# Fan_Module.net
KiCad netlist of a schematic drawn in Altium Designer
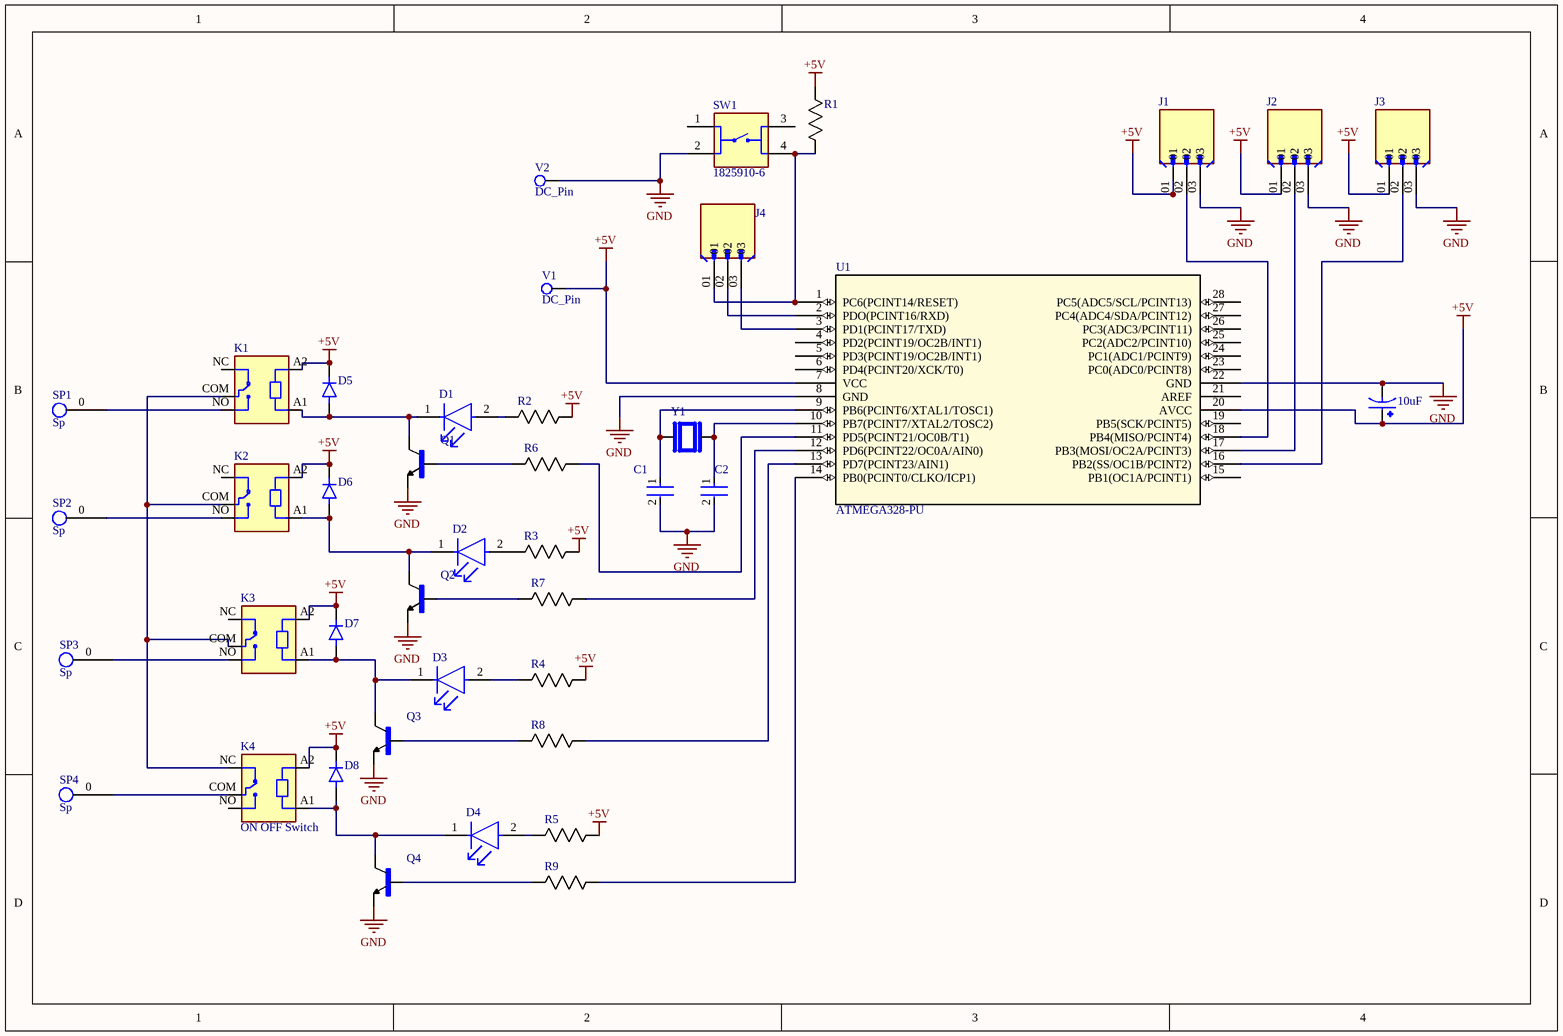
[diagram p0: Fan_Module.SchDoc]

(export (version "E")
  (design (tool "Eeschema 10.0.6"))
  (components
    (comp (ref "10uF")
      (value "ECEA1HN100UI")
      (footprint "Fan_Module_PcbLib:CAPPRD250W50D630H1120")
      (description "CAP ALUM 10UF 20% 50V RADIAL")
      (fields (field (name "MP") "ECE-A1HN100UI") (field (name "MF") "Panasonic"))
      (libsource (lib "Fan_Module_SchiLib") (part "ECEA1HN100UI"))
    )
    (comp (ref "C1")
      (value "RDE5C2A220J0M1H03A")
      (footprint "FP-RDE0M1-MFG")
      (description "Ceramic Capacitor 22pF ±5% 100V C0G Radial")
      (fields (field (name "TOLERANCE") "5%"))
      (libsource (lib "Fan_Module_SchiLib") (part "CMP-06035-022985-1"))
    )
    (comp (ref "C2")
      (value "RDE5C2A220J0M1H03A")
      (footprint "FP-RDE0M1-MFG")
      (description "Ceramic Capacitor 22pF ±5% 100V C0G Radial")
      (fields (field (name "TOLERANCE") "5%"))
      (libsource (lib "Fan_Module_SchiLib") (part "CMP-06035-022985-1"))
    )
    (comp (ref "D1")
      (value "TSFF5210")
      (footprint "FP-6_544-5258_09-4-MFG")
      (description "TSFF5210 TSFF5210 IR LED, 870nm, T-1 3/4 (5mm) Through Hole package ¦ Siliconix / Vishay TSFF5210")
      (libsource (lib "Fan_Module_SchiLib") (part "CMP-00030-41223146-1"))
    )
    (comp (ref "D2")
      (value "TSFF5210")
      (footprint "FP-6_544-5258_09-4-MFG")
      (description "TSFF5210 TSFF5210 IR LED, 870nm, T-1 3/4 (5mm) Through Hole package ¦ Siliconix / Vishay TSFF5210")
      (libsource (lib "Fan_Module_SchiLib") (part "CMP-00030-41223146-1"))
    )
    (comp (ref "D3")
      (value "TSFF5210")
      (footprint "FP-6_544-5258_09-4-MFG")
      (description "TSFF5210 TSFF5210 IR LED, 870nm, T-1 3/4 (5mm) Through Hole package ¦ Siliconix / Vishay TSFF5210")
      (libsource (lib "Fan_Module_SchiLib") (part "CMP-00030-41223146-1"))
    )
    (comp (ref "D4")
      (value "TSFF5210")
      (footprint "FP-6_544-5258_09-4-MFG")
      (description "TSFF5210 TSFF5210 IR LED, 870nm, T-1 3/4 (5mm) Through Hole package ¦ Siliconix / Vishay TSFF5210")
      (libsource (lib "Fan_Module_SchiLib") (part "CMP-00030-41223146-1"))
    )
    (comp (ref "D5")
      (value "1N4007G")
      (footprint "DIOAD1036W78L470D235")
      (description "1A, 1000V, Standard Recovery Rectifier")
      (fields (field (name "MF") "Taiwan Semiconductor"))
      (libsource (lib "Fan_Module_SchiLib") (part "1N4007G"))
    )
    (comp (ref "D6")
      (value "1N4007G")
      (footprint "DIOAD1036W78L470D235")
      (description "1A, 1000V, Standard Recovery Rectifier")
      (fields (field (name "MF") "Taiwan Semiconductor"))
      (libsource (lib "Fan_Module_SchiLib") (part "1N4007G"))
    )
    (comp (ref "D7")
      (value "1N4007G")
      (footprint "DIOAD1036W78L470D235")
      (description "1A, 1000V, Standard Recovery Rectifier")
      (fields (field (name "MF") "Taiwan Semiconductor"))
      (libsource (lib "Fan_Module_SchiLib") (part "1N4007G"))
    )
    (comp (ref "D8")
      (value "1N4007G")
      (footprint "DIOAD1036W78L470D235")
      (description "1A, 1000V, Standard Recovery Rectifier")
      (fields (field (name "MF") "Taiwan Semiconductor"))
      (libsource (lib "Fan_Module_SchiLib") (part "1N4007G"))
    )
    (comp (ref "J1")
      (value "68001-203HLF")
      (footprint "AMPHENOL_68001-203HLF")
      (fields (field (name "MF") "Amphenol ICC"))
      (libsource (lib "Fan_Module_SchiLib") (part "68001-203HLF"))
    )
    (comp (ref "J2")
      (value "68001-203HLF")
      (footprint "AMPHENOL_68001-203HLF")
      (fields (field (name "MF") "Amphenol ICC"))
      (libsource (lib "Fan_Module_SchiLib") (part "68001-203HLF"))
    )
    (comp (ref "J3")
      (value "68001-203HLF")
      (footprint "AMPHENOL_68001-203HLF")
      (fields (field (name "MF") "Amphenol ICC"))
      (libsource (lib "Fan_Module_SchiLib") (part "68001-203HLF"))
    )
    (comp (ref "J4")
      (value "68001-203HLF")
      (footprint "AMPHENOL_68001-203HLF")
      (fields (field (name "MF") "Amphenol ICC"))
      (libsource (lib "Fan_Module_SchiLib") (part "68001-203HLF"))
    )
    (comp (ref "K1")
      (value "SRD-05VDC-SL-C")
      (footprint "RELAY_SRD-05VDC-SL-C")
      (fields (field (name "MF") "Songle Relay"))
      (libsource (lib "Fan_Module_SchiLib") (part "SRD-05VDC-SL-C"))
    )
    (comp (ref "K2")
      (value "SRD-05VDC-SL-C")
      (footprint "RELAY_SRD-05VDC-SL-C")
      (fields (field (name "MF") "Songle Relay"))
      (libsource (lib "Fan_Module_SchiLib") (part "SRD-05VDC-SL-C"))
    )
    (comp (ref "K3")
      (value "SRD-05VDC-SL-C")
      (footprint "RELAY_SRD-05VDC-SL-C")
      (fields (field (name "MF") "Songle Relay"))
      (libsource (lib "Fan_Module_SchiLib") (part "SRD-05VDC-SL-C"))
    )
    (comp (ref "K4")
      (value "ON OFF Switch")
      (footprint "RELAY_SRD-05VDC-SL-C")
      (fields (field (name "MF") "Songle Relay") (field (name "MP") "SRD-05VDC-SL-C"))
      (libsource (lib "Fan_Module_SchiLib") (part "SRD-05VDC-SL-C"))
    )
    (comp (ref "Q1")
      (value "2N3904")
      (footprint "TO92127P495H495-3")
      (description "TRANS NPN 40V 200MA TO92-3")
      (fields (field (name "MF") "Rectron"))
      (libsource (lib "Fan_Module_SchiLib") (part "2N3904"))
    )
    (comp (ref "Q2")
      (value "2N3904")
      (footprint "TO92127P495H495-3")
      (description "TRANS NPN 40V 200MA TO92-3")
      (fields (field (name "MF") "Rectron"))
      (libsource (lib "Fan_Module_SchiLib") (part "2N3904"))
    )
    (comp (ref "Q3")
      (value "2N3904")
      (footprint "TO92127P495H495-3")
      (description "TRANS NPN 40V 200MA TO92-3")
      (fields (field (name "MF") "Rectron"))
      (libsource (lib "Fan_Module_SchiLib") (part "2N3904"))
    )
    (comp (ref "Q4")
      (value "2N3904")
      (footprint "TO92127P495H495-3")
      (description "TRANS NPN 40V 200MA TO92-3")
      (fields (field (name "MF") "Rectron"))
      (libsource (lib "Fan_Module_SchiLib") (part "2N3904"))
    )
    (comp (ref "R1")
      (value "MFR-25FRF52-10K")
      (footprint "YAG_MF25_YAG")
      (description "No Description Available")
      (libsource (lib "Fan_Module_SchiLib") (part "MFR-25FRF52-10K"))
    )
    (comp (ref "R2")
      (value "MFR-25FRF52-10K")
      (footprint "YAG_MF25_YAG")
      (description "No Description Available")
      (libsource (lib "Fan_Module_SchiLib") (part "MFR-25FRF52-10K"))
    )
    (comp (ref "R3")
      (value "MFR-25FRF52-10K")
      (footprint "YAG_MF25_YAG")
      (description "No Description Available")
      (libsource (lib "Fan_Module_SchiLib") (part "MFR-25FRF52-10K"))
    )
    (comp (ref "R4")
      (value "MFR-25FRF52-10K")
      (footprint "YAG_MF25_YAG")
      (description "No Description Available")
      (libsource (lib "Fan_Module_SchiLib") (part "MFR-25FRF52-10K"))
    )
    (comp (ref "R5")
      (value "MFR-25FRF52-10K")
      (footprint "YAG_MF25_YAG")
      (description "No Description Available")
      (libsource (lib "Fan_Module_SchiLib") (part "MFR-25FRF52-10K"))
    )
    (comp (ref "R6")
      (value "MFR-25FRF52-10K")
      (footprint "YAG_MF25_YAG")
      (description "No Description Available")
      (libsource (lib "Fan_Module_SchiLib") (part "MFR-25FRF52-10K"))
    )
    (comp (ref "R7")
      (value "MFR-25FRF52-10K")
      (footprint "YAG_MF25_YAG")
      (description "No Description Available")
      (libsource (lib "Fan_Module_SchiLib") (part "MFR-25FRF52-10K"))
    )
    (comp (ref "R8")
      (value "MFR-25FRF52-10K")
      (footprint "YAG_MF25_YAG")
      (description "No Description Available")
      (libsource (lib "Fan_Module_SchiLib") (part "MFR-25FRF52-10K"))
    )
    (comp (ref "R9")
      (value "MFR-25FRF52-10K")
      (footprint "YAG_MF25_YAG")
      (description "No Description Available")
      (libsource (lib "Fan_Module_SchiLib") (part "MFR-25FRF52-10K"))
    )
    (comp (ref "SP1")
      (value "Sp")
      (footprint "solderPoint")
      (libsource (lib "Fan_Module_SchiLib") (part "soldPoint"))
    )
    (comp (ref "SP2")
      (value "Sp")
      (footprint "solderPoint")
      (libsource (lib "Fan_Module_SchiLib") (part "soldPoint"))
    )
    (comp (ref "SP3")
      (value "Sp")
      (footprint "solderPoint")
      (libsource (lib "Fan_Module_SchiLib") (part "soldPoint"))
    )
    (comp (ref "SP4")
      (value "Sp")
      (footprint "solderPoint")
      (libsource (lib "Fan_Module_SchiLib") (part "soldPoint"))
    )
    (comp (ref "SW1")
      (value "1825910-6")
      (footprint "SW_1825910-6-4")
      (description "Switch Push Button OFF (ON) SPST Round Button 0.05A 24VDC Momentary Contact PC Pins Thru-Hole")
      (fields (field (name "MF") "TE Connectivity") (field (name "DIGI-KEY_PART_NUMBER") "450-1650-ND"))
      (libsource (lib "Fan_Module_SchiLib") (part "1825910-6"))
    )
    (comp (ref "U1")
      (value "ATMEGA328-PU")
      (footprint "28P3_SPDIP28_SP_MCH")
      (description "No Description Available")
      (libsource (lib "Fan_Module_SchiLib") (part "ATMEGA328-PU"))
    )
    (comp (ref "V1")
      (value "DC_Pin")
      (footprint "DC_Pin")
      (libsource (lib "Fan_Module_SchiLib") (part "DC_Pin"))
    )
    (comp (ref "V2")
      (value "DC_Pin")
      (footprint "DC_Pin")
      (libsource (lib "Fan_Module_SchiLib") (part "DC_Pin"))
    )
    (comp (ref "Y1")
      (value "ABL-16.000MHZ-B2")
      (footprint "XTAL_HC49P488W46L1150T500H350")
      (description "HC/49US (AT49) MICROPROCESSOR CRYSTAL")
      (fields (field (name "MF") "Abracon"))
      (libsource (lib "Fan_Module_SchiLib") (part "ABL-16.000MHZ-B2"))
    )
  )
  (nets
    (net (code "1") (name "+5V") (class "Default")
      (node (ref "10uF") (pin "P") (pinfunction "P_P") (pintype "passive"))
      (node (ref "D5") (pin "C") (pinfunction "K_C") (pintype "passive"))
      (node (ref "D6") (pin "C") (pinfunction "K_C") (pintype "passive"))
      (node (ref "D7") (pin "C") (pinfunction "K_C") (pintype "passive"))
      (node (ref "D8") (pin "C") (pinfunction "K_C") (pintype "passive"))
      (node (ref "J1") (pin "01") (pinfunction "01_01") (pintype "passive"))
      (node (ref "J2") (pin "01") (pinfunction "01_01") (pintype "passive"))
      (node (ref "J3") (pin "01") (pinfunction "01_01") (pintype "passive"))
      (node (ref "K1") (pin "A2") (pinfunction "A2_A2") (pintype "passive"))
      (node (ref "K2") (pin "A2") (pinfunction "A2_A2") (pintype "passive"))
      (node (ref "K3") (pin "A2") (pinfunction "A2_A2") (pintype "passive"))
      (node (ref "K4") (pin "A2") (pinfunction "A2_A2") (pintype "passive"))
      (node (ref "R1") (pin "2") (pinfunction "2_2") (pintype "passive"))
      (node (ref "R2") (pin "2") (pinfunction "2_2") (pintype "passive"))
      (node (ref "R3") (pin "2") (pinfunction "2_2") (pintype "passive"))
      (node (ref "R4") (pin "2") (pinfunction "2_2") (pintype "passive"))
      (node (ref "R5") (pin "2") (pinfunction "2_2") (pintype "passive"))
      (node (ref "U1") (pin "20") (pinfunction "AVCC_20") (pintype "power_in"))
      (node (ref "U1") (pin "7") (pinfunction "VCC_7") (pintype "power_in"))
      (node (ref "V1") (pin "0") (pinfunction "0_0") (pintype "passive"))
    )
    (net (code "2") (name "GND") (class "Default")
      (node (ref "10uF") (pin "N") (pinfunction "N_N") (pintype "passive"))
      (node (ref "C1") (pin "2") (pinfunction "2_2") (pintype "passive"))
      (node (ref "C2") (pin "2") (pinfunction "2_2") (pintype "passive"))
      (node (ref "J1") (pin "03") (pinfunction "03_03") (pintype "passive"))
      (node (ref "J2") (pin "03") (pinfunction "03_03") (pintype "passive"))
      (node (ref "J3") (pin "03") (pinfunction "03_03") (pintype "passive"))
      (node (ref "Q1") (pin "1") (pinfunction "E_1") (pintype "passive"))
      (node (ref "Q2") (pin "1") (pinfunction "E_1") (pintype "passive"))
      (node (ref "Q3") (pin "1") (pinfunction "E_1") (pintype "passive"))
      (node (ref "Q4") (pin "1") (pinfunction "E_1") (pintype "passive"))
      (node (ref "SW1") (pin "2") (pinfunction "2_2") (pintype "passive"))
      (node (ref "U1") (pin "22") (pinfunction "GND_22") (pintype "power_in"))
      (node (ref "U1") (pin "8") (pinfunction "GND_8") (pintype "power_in"))
      (node (ref "V2") (pin "0") (pinfunction "0_0") (pintype "passive"))
    )
    (net (code "3") (name "Net-(D1-A)") (class "Default")
      (node (ref "D1") (pin "2") (pinfunction "A_2") (pintype "passive"))
      (node (ref "R2") (pin "1") (pinfunction "1_1") (pintype "passive"))
    )
    (net (code "4") (name "Net-(D1-C)") (class "Default")
      (node (ref "D1") (pin "1") (pinfunction "C_1") (pintype "passive"))
      (node (ref "D5") (pin "A") (pinfunction "A_A") (pintype "passive"))
      (node (ref "K1") (pin "A1") (pinfunction "A1_A1") (pintype "passive"))
      (node (ref "Q1") (pin "3") (pinfunction "C_3") (pintype "passive"))
    )
    (net (code "5") (name "Net-(D2-A)") (class "Default")
      (node (ref "D2") (pin "2") (pinfunction "A_2") (pintype "passive"))
      (node (ref "R3") (pin "1") (pinfunction "1_1") (pintype "passive"))
    )
    (net (code "6") (name "Net-(D2-C)") (class "Default")
      (node (ref "D2") (pin "1") (pinfunction "C_1") (pintype "passive"))
      (node (ref "D6") (pin "A") (pinfunction "A_A") (pintype "passive"))
      (node (ref "K2") (pin "A1") (pinfunction "A1_A1") (pintype "passive"))
      (node (ref "Q2") (pin "3") (pinfunction "C_3") (pintype "passive"))
    )
    (net (code "7") (name "Net-(D3-A)") (class "Default")
      (node (ref "D3") (pin "2") (pinfunction "A_2") (pintype "passive"))
      (node (ref "R4") (pin "1") (pinfunction "1_1") (pintype "passive"))
    )
    (net (code "8") (name "Net-(D3-C)") (class "Default")
      (node (ref "D3") (pin "1") (pinfunction "C_1") (pintype "passive"))
      (node (ref "D7") (pin "A") (pinfunction "A_A") (pintype "passive"))
      (node (ref "K3") (pin "A1") (pinfunction "A1_A1") (pintype "passive"))
      (node (ref "Q3") (pin "3") (pinfunction "C_3") (pintype "passive"))
    )
    (net (code "9") (name "Net-(D4-A)") (class "Default")
      (node (ref "D4") (pin "2") (pinfunction "A_2") (pintype "passive"))
      (node (ref "R5") (pin "1") (pinfunction "1_1") (pintype "passive"))
    )
    (net (code "10") (name "Net-(D4-C)") (class "Default")
      (node (ref "D4") (pin "1") (pinfunction "C_1") (pintype "passive"))
      (node (ref "D8") (pin "A") (pinfunction "A_A") (pintype "passive"))
      (node (ref "K4") (pin "A1") (pinfunction "A1_A1") (pintype "passive"))
      (node (ref "Q4") (pin "3") (pinfunction "C_3") (pintype "passive"))
    )
    (net (code "11") (name "Net-(K1-PadCOM)") (class "Default")
      (node (ref "K1") (pin "COM") (pinfunction "COM_COM") (pintype "passive"))
      (node (ref "K2") (pin "COM") (pinfunction "COM_COM") (pintype "passive"))
      (node (ref "K3") (pin "COM") (pinfunction "COM_COM") (pintype "passive"))
      (node (ref "K4") (pin "NC") (pinfunction "NC_NC") (pintype "passive"))
    )
    (net (code "12") (name "Net-(K1-PadNO)") (class "Default")
      (node (ref "K1") (pin "NO") (pinfunction "NO_NO") (pintype "passive"))
      (node (ref "SP1") (pin "0") (pinfunction "0_0") (pintype "passive"))
    )
    (net (code "13") (name "Net-(K2-PadNO)") (class "Default")
      (node (ref "K2") (pin "NO") (pinfunction "NO_NO") (pintype "passive"))
      (node (ref "SP2") (pin "0") (pinfunction "0_0") (pintype "passive"))
    )
    (net (code "14") (name "Net-(K3-PadNO)") (class "Default")
      (node (ref "K3") (pin "NO") (pinfunction "NO_NO") (pintype "passive"))
      (node (ref "SP3") (pin "0") (pinfunction "0_0") (pintype "passive"))
    )
    (net (code "15") (name "Net-(K4-PadCOM)") (class "Default")
      (node (ref "K4") (pin "COM") (pinfunction "COM_COM") (pintype "passive"))
      (node (ref "SP4") (pin "0") (pinfunction "0_0") (pintype "passive"))
    )
    (net (code "16") (name "Net-(Q1-B)") (class "Default")
      (node (ref "Q1") (pin "2") (pinfunction "B_2") (pintype "passive"))
      (node (ref "R6") (pin "1") (pinfunction "1_1") (pintype "passive"))
    )
    (net (code "17") (name "Net-(Q2-B)") (class "Default")
      (node (ref "Q2") (pin "2") (pinfunction "B_2") (pintype "passive"))
      (node (ref "R7") (pin "1") (pinfunction "1_1") (pintype "passive"))
    )
    (net (code "18") (name "Net-(Q3-B)") (class "Default")
      (node (ref "Q3") (pin "2") (pinfunction "B_2") (pintype "passive"))
      (node (ref "R8") (pin "1") (pinfunction "1_1") (pintype "passive"))
    )
    (net (code "19") (name "Net-(Q4-B)") (class "Default")
      (node (ref "Q4") (pin "2") (pinfunction "B_2") (pintype "passive"))
      (node (ref "R9") (pin "1") (pinfunction "1_1") (pintype "passive"))
    )
    (net (code "20") (name "Net-(U1-PB0(PCINT0{slash}CLKO{slash}ICP1))") (class "Default")
      (node (ref "R9") (pin "2") (pinfunction "2_2") (pintype "passive"))
      (node (ref "U1") (pin "14") (pinfunction "PB0(PCINT0/CLKO/ICP1)_14") (pintype "bidirectional"))
    )
    (net (code "21") (name "Net-(U1-PB2(SS{slash}OC1B{slash}PCINT2))") (class "Default")
      (node (ref "J3") (pin "02") (pinfunction "02_02") (pintype "passive"))
      (node (ref "U1") (pin "16") (pinfunction "PB2(SS/OC1B/PCINT2)_16") (pintype "bidirectional"))
    )
    (net (code "22") (name "Net-(U1-PB3(MOSI{slash}OC2A{slash}PCINT3))") (class "Default")
      (node (ref "J2") (pin "02") (pinfunction "02_02") (pintype "passive"))
      (node (ref "U1") (pin "17") (pinfunction "PB3(MOSI/OC2A/PCINT3)_17") (pintype "bidirectional"))
    )
    (net (code "23") (name "Net-(U1-PB4(MISO{slash}PCINT4))") (class "Default")
      (node (ref "J1") (pin "02") (pinfunction "02_02") (pintype "passive"))
      (node (ref "U1") (pin "18") (pinfunction "PB4(MISO/PCINT4)_18") (pintype "bidirectional"))
    )
    (net (code "24") (name "Net-(U1-PB6(PCINT6{slash}XTAL1{slash}TOSC1))") (class "Default")
      (node (ref "C1") (pin "1") (pinfunction "1_1") (pintype "passive"))
      (node (ref "U1") (pin "9") (pinfunction "PB6(PCINT6/XTAL1/TOSC1)_9") (pintype "bidirectional"))
      (node (ref "Y1") (pin "1") (pinfunction "1_1") (pintype "passive"))
    )
    (net (code "25") (name "Net-(U1-PB7(PCINT7{slash}XTAL2{slash}TOSC2))") (class "Default")
      (node (ref "C2") (pin "1") (pinfunction "1_1") (pintype "passive"))
      (node (ref "U1") (pin "10") (pinfunction "PB7(PCINT7/XTAL2/TOSC2)_10") (pintype "bidirectional"))
      (node (ref "Y1") (pin "2") (pinfunction "2_2") (pintype "passive"))
    )
    (net (code "26") (name "Net-(U1-PC6(PCINT14{slash}RESET))") (class "Default")
      (node (ref "J4") (pin "01") (pinfunction "01_01") (pintype "passive"))
      (node (ref "R1") (pin "1") (pinfunction "1_1") (pintype "passive"))
      (node (ref "SW1") (pin "4") (pinfunction "4_4") (pintype "passive"))
      (node (ref "U1") (pin "1") (pinfunction "PC6(PCINT14/RESET)_1") (pintype "bidirectional"))
    )
    (net (code "27") (name "Net-(U1-PD1(PCINT17{slash}TXD))") (class "Default")
      (node (ref "J4") (pin "03") (pinfunction "03_03") (pintype "passive"))
      (node (ref "U1") (pin "3") (pinfunction "PD1(PCINT17/TXD)_3") (pintype "bidirectional"))
    )
    (net (code "28") (name "Net-(U1-PD5(PCINT21{slash}OC0B{slash}T1))") (class "Default")
      (node (ref "R6") (pin "2") (pinfunction "2_2") (pintype "passive"))
      (node (ref "U1") (pin "11") (pinfunction "PD5(PCINT21/OC0B/T1)_11") (pintype "bidirectional"))
    )
    (net (code "29") (name "Net-(U1-PD6(PCINT22{slash}OC0A{slash}AIN0))") (class "Default")
      (node (ref "R7") (pin "2") (pinfunction "2_2") (pintype "passive"))
      (node (ref "U1") (pin "12") (pinfunction "PD6(PCINT22/OC0A/AIN0)_12") (pintype "bidirectional"))
    )
    (net (code "30") (name "Net-(U1-PD7(PCINT23{slash}AIN1))") (class "Default")
      (node (ref "R8") (pin "2") (pinfunction "2_2") (pintype "passive"))
      (node (ref "U1") (pin "13") (pinfunction "PD7(PCINT23/AIN1)_13") (pintype "bidirectional"))
    )
    (net (code "31") (name "Net-(U1-PDO(PCINT16{slash}RXD))") (class "Default")
      (node (ref "J4") (pin "02") (pinfunction "02_02") (pintype "passive"))
      (node (ref "U1") (pin "2") (pinfunction "PDO(PCINT16/RXD)_2") (pintype "bidirectional"))
    )
    (net (code "32") (name "unconnected-(K1-PadNC)") (class "Default")
      (node (ref "K1") (pin "NC") (pinfunction "NC_NC") (pintype "passive"))
    )
    (net (code "33") (name "unconnected-(K2-PadNC)") (class "Default")
      (node (ref "K2") (pin "NC") (pinfunction "NC_NC") (pintype "passive"))
    )
    (net (code "34") (name "unconnected-(K3-PadNC)") (class "Default")
      (node (ref "K3") (pin "NC") (pinfunction "NC_NC") (pintype "passive"))
    )
    (net (code "35") (name "unconnected-(K4-PadNO)") (class "Default")
      (node (ref "K4") (pin "NO") (pinfunction "NO_NO") (pintype "passive"))
    )
    (net (code "36") (name "unconnected-(SW1-Pad1)") (class "Default")
      (node (ref "SW1") (pin "1") (pinfunction "1_1") (pintype "passive"))
    )
    (net (code "37") (name "unconnected-(SW1-Pad3)") (class "Default")
      (node (ref "SW1") (pin "3") (pinfunction "3_3") (pintype "passive"))
    )
    (net (code "38") (name "unconnected-(U1-AREF-Pad21)") (class "Default")
      (node (ref "U1") (pin "21") (pinfunction "AREF_21") (pintype "passive"))
    )
    (net (code "39") (name "unconnected-(U1-PB1(OC1A{slash}PCINT1)-Pad15)") (class "Default")
      (node (ref "U1") (pin "15") (pinfunction "PB1(OC1A/PCINT1)_15") (pintype "bidirectional"))
    )
    (net (code "40") (name "unconnected-(U1-PB5(SCK{slash}PCINT5)-Pad19)") (class "Default")
      (node (ref "U1") (pin "19") (pinfunction "PB5(SCK/PCINT5)_19") (pintype "bidirectional"))
    )
    (net (code "41") (name "unconnected-(U1-PC0(ADC0{slash}PCINT8)-Pad23)") (class "Default")
      (node (ref "U1") (pin "23") (pinfunction "PC0(ADC0/PCINT8)_23") (pintype "bidirectional"))
    )
    (net (code "42") (name "unconnected-(U1-PC1(ADC1{slash}PCINT9)-Pad24)") (class "Default")
      (node (ref "U1") (pin "24") (pinfunction "PC1(ADC1/PCINT9)_24") (pintype "bidirectional"))
    )
    (net (code "43") (name "unconnected-(U1-PC2(ADC2{slash}PCINT10)-Pad25)") (class "Default")
      (node (ref "U1") (pin "25") (pinfunction "PC2(ADC2/PCINT10)_25") (pintype "bidirectional"))
    )
    (net (code "44") (name "unconnected-(U1-PC3(ADC3{slash}PCINT11)-Pad26)") (class "Default")
      (node (ref "U1") (pin "26") (pinfunction "PC3(ADC3/PCINT11)_26") (pintype "bidirectional"))
    )
    (net (code "45") (name "unconnected-(U1-PC4(ADC4{slash}SDA{slash}PCINT12)-Pad27)") (class "Default")
      (node (ref "U1") (pin "27") (pinfunction "PC4(ADC4/SDA/PCINT12)_27") (pintype "bidirectional"))
    )
    (net (code "46") (name "unconnected-(U1-PC5(ADC5{slash}SCL{slash}PCINT13)-Pad28)") (class "Default")
      (node (ref "U1") (pin "28") (pinfunction "PC5(ADC5/SCL/PCINT13)_28") (pintype "bidirectional"))
    )
    (net (code "47") (name "unconnected-(U1-PD2(PCINT19{slash}OC2B{slash}INT1)-Pad4)") (class "Default")
      (node (ref "U1") (pin "4") (pinfunction "PD2(PCINT19/OC2B/INT1)_4") (pintype "bidirectional"))
    )
    (net (code "48") (name "unconnected-(U1-PD3(PCINT19{slash}OC2B{slash}INT1)-Pad5)") (class "Default")
      (node (ref "U1") (pin "5") (pinfunction "PD3(PCINT19/OC2B/INT1)_5") (pintype "bidirectional"))
    )
    (net (code "49") (name "unconnected-(U1-PD4(PCINT20{slash}XCK{slash}T0)-Pad6)") (class "Default")
      (node (ref "U1") (pin "6") (pinfunction "PD4(PCINT20/XCK/T0)_6") (pintype "bidirectional"))
    )
  )
)
